# butt-on-mk-1_3.net
KiCad netlist of a schematic drawn in EAGLE
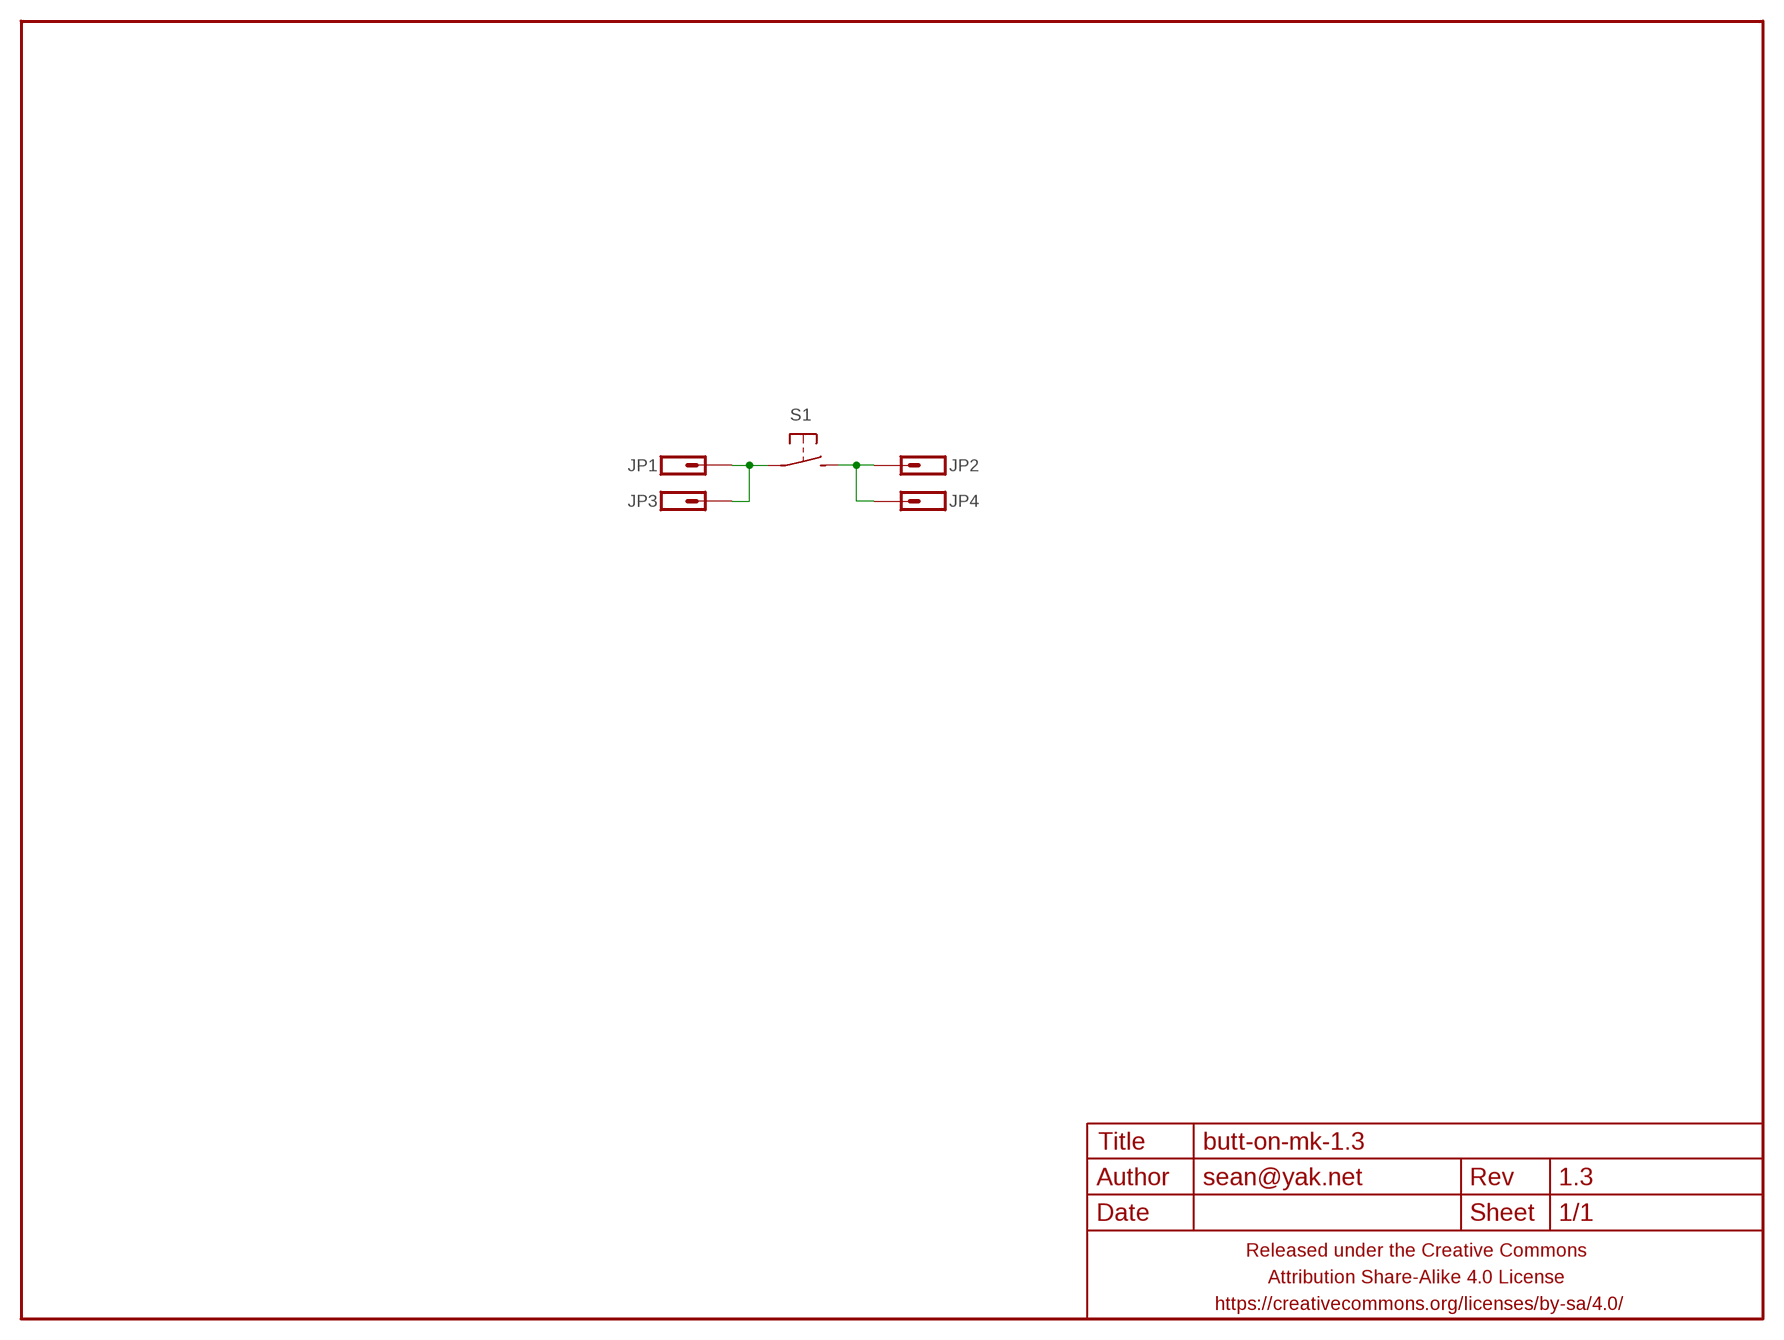
[diagram p0: schematic, sheet 1]

(export (version "E")
  (design (tool "Eeschema 10.0.6"))
  (components
    (comp (ref "FRAME1")
      (value "FRAME-LETTERNO_PACKAGE")
      (footprint "eagle-import:DUMMY")
      (fields (field (name "DESIGNER") "sean@yak.net") (field (name "VERSION") "1.3"))
      (libsource (lib "eagle-import") (part "FRAME-LETTERNO_PACKAGE"))
    )
    (comp (ref "JP1")
      (value "M01PTH-0.9MM-NS")
      (footprint "eagle-import:1X01-0.9MM-NS")
      (libsource (lib "eagle-import") (part "M01PTH-0.9MM-NS"))
    )
    (comp (ref "JP2")
      (value "M01PTH-0.9MM-NS")
      (footprint "eagle-import:1X01-0.9MM-NS")
      (libsource (lib "eagle-import") (part "M01PTH-0.9MM-NS"))
    )
    (comp (ref "JP3")
      (value "M01PTH-0.9MM-NS")
      (footprint "eagle-import:1X01-0.9MM-NS")
      (libsource (lib "eagle-import") (part "M01PTH-0.9MM-NS"))
    )
    (comp (ref "JP4")
      (value "M01PTH-0.9MM-NS")
      (footprint "eagle-import:1X01-0.9MM-NS")
      (libsource (lib "eagle-import") (part "M01PTH-0.9MM-NS"))
    )
    (comp (ref "S1")
      (value "SPST-NO-TACT6MM-PTH-SMALL-PADS")
      (footprint "eagle-import:DTS-6-SMALL-PADS")
      (libsource (lib "eagle-import") (part "SPST-NO-TACT6MM-PTH-SMALL-PADS"))
    )
  )
  (nets
    (net (code "1") (name "Net-(JP1-Pad1)") (class "Default")
      (node (ref "JP1") (pin "1") (pinfunction "1_1") (pintype "passive"))
      (node (ref "JP3") (pin "1") (pinfunction "1_1") (pintype "passive"))
      (node (ref "S1") (pin "1") (pinfunction "1_1") (pintype "passive"))
      (node (ref "S1") (pin "2") (pinfunction "1_2") (pintype "passive"))
    )
    (net (code "2") (name "Net-(JP2-Pad1)") (class "Default")
      (node (ref "JP2") (pin "1") (pinfunction "1_1") (pintype "passive"))
      (node (ref "JP4") (pin "1") (pinfunction "1_1") (pintype "passive"))
      (node (ref "S1") (pin "3") (pinfunction "2_3") (pintype "passive"))
      (node (ref "S1") (pin "4") (pinfunction "2_4") (pintype "passive"))
    )
  )
)
